# BMS.net
KiCad netlist of a schematic drawn in Altium Designer
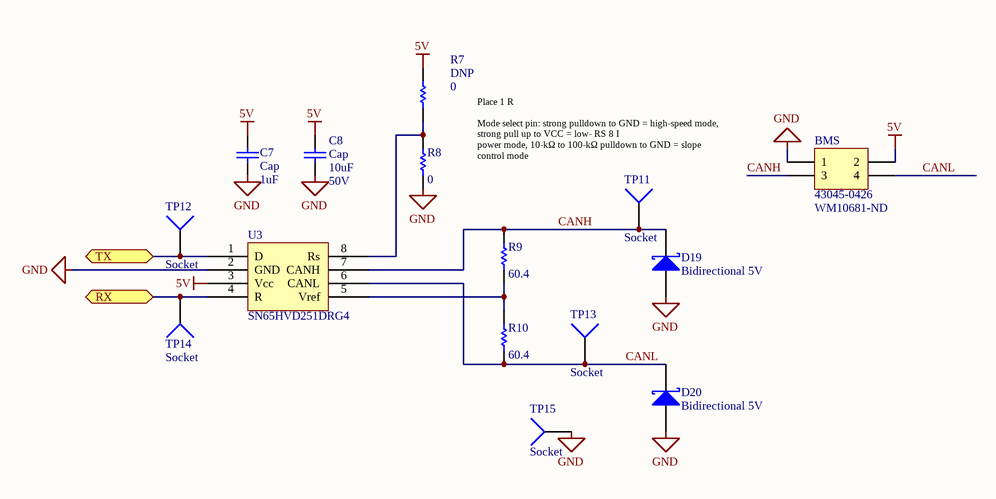
[diagram p0: BMS.SchDoc]

(export (version "E")
  (design (tool "Eeschema 10.0.6"))
  (components
    (comp (ref "BMS")
      (value "43045-0426")
      (footprint "43045-0426")
      (description "Header, 2-Pin, Dual row")
      (fields (field (name "VENDOR PART NUMBER") "WM10681-ND") (field (name "PUBLISHER") "Altium Limited"))
      (libsource (lib "Miscellaneous Connectors") (part "Header 2X2"))
    )
    (comp (ref "C7")
      (value "Cap")
      (footprint "RESC3116X65N")
      (description "Capacitor")
      (fields
        (field (name "ALTIUM_VALUE") "1uF")
        (field (name "MANUFACTURER PART NUMBER") "CL31B105KCHNNNE")
        (field (name "VENDOR PART NUMBER") "1276-1838-1-ND")
      )
      (libsource (lib "Miscellaneous Devices") (part "Cap"))
    )
    (comp (ref "C8")
      (value "Cap")
      (footprint "CAPC3216X180N")
      (description "Capacitor")
      (fields
        (field (name "ALTIUM_VALUE") "10uF")
        (field (name "MANUFACTURER PART NUMBER") "CL31A106MBHNNNE")
        (field (name "VENDOR PART NUMBER") "1276-6736-1-ND")
        (field (name "VOLTAGE RATING") "50V")
      )
      (libsource (lib "Miscellaneous Devices") (part "Cap"))
    )
    (comp (ref "D19")
      (value "Bidirectional 5V")
      (footprint "THRMC0603X33N")
      (description "TVS")
      (fields
        (field (name "MANUFACTURER PART NUMBER") "CPDUC5V0R-HF")
        (field (name "VENDOR PART NUMBER") "641-1764-1-ND")
      )
      (libsource (lib "Miscellaneous Devices") (part "Diode 10TQ040"))
    )
    (comp (ref "D20")
      (value "Bidirectional 5V")
      (footprint "THRMC0603X33N")
      (description "TVS")
      (fields
        (field (name "MANUFACTURER PART NUMBER") "CPDUC5V0R-HF")
        (field (name "VENDOR PART NUMBER") "641-1764-1-ND")
      )
      (libsource (lib "Miscellaneous Devices") (part "Diode 10TQ040"))
    )
    (comp (ref "R7")
      (value "0")
      (footprint "0402")
      (description "Resistor")
      (fields
        (field (name "MANUFACTURER PART NUMBER") "RC0402FR-070RL")
        (field (name "VENDOR PART NUMBER") "311-0.0LRCT-ND")
        (field (name "DNP") "DNP")
      )
      (libsource (lib "Miscellaneous Devices") (part "Res1"))
    )
    (comp (ref "R8")
      (value "0")
      (footprint "0402")
      (description "Resistor")
      (fields
        (field (name "MANUFACTURER PART NUMBER") "RC0402FR-070RL")
        (field (name "VENDOR PART NUMBER") "311-0.0LRCT-ND")
      )
      (libsource (lib "Miscellaneous Devices") (part "Res1"))
    )
    (comp (ref "R9")
      (value "60.4")
      (footprint "0402")
      (description "Resistor")
      (fields
        (field (name "MANUFACTURER PART NUMBER") "RC0402FR-0760R4L")
        (field (name "VENDOR PART NUMBER") "311-60.4LRCT-ND")
      )
      (libsource (lib "Miscellaneous Devices") (part "Res1"))
    )
    (comp (ref "R10")
      (value "60.4")
      (footprint "0402")
      (description "Resistor")
      (fields
        (field (name "MANUFACTURER PART NUMBER") "RC0402FR-0760R4L")
        (field (name "VENDOR PART NUMBER") "311-60.4LRCT-ND")
      )
      (libsource (lib "Miscellaneous Devices") (part "Res1"))
    )
    (comp (ref "TP11")
      (value "Socket")
      (footprint "5006")
      (fields
        (field (name "MANUFACTURER PART NUMBER") "5006")
        (field (name "VENDOR PART NUMBER") "36-5006-ND")
        (field (name "PUBLISHER") "Altium Limited")
      )
      (libsource (lib "Miscellaneous Connectors") (part "Socket"))
    )
    (comp (ref "TP12")
      (value "Socket")
      (footprint "5006")
      (fields
        (field (name "MANUFACTURER PART NUMBER") "5006")
        (field (name "VENDOR PART NUMBER") "36-5006-ND")
        (field (name "PUBLISHER") "Altium Limited")
      )
      (libsource (lib "Miscellaneous Connectors") (part "Socket"))
    )
    (comp (ref "TP13")
      (value "Socket")
      (footprint "5006")
      (fields
        (field (name "MANUFACTURER PART NUMBER") "5006")
        (field (name "VENDOR PART NUMBER") "36-5006-ND")
        (field (name "PUBLISHER") "Altium Limited")
      )
      (libsource (lib "Miscellaneous Connectors") (part "Socket"))
    )
    (comp (ref "TP14")
      (value "Socket")
      (footprint "5006")
      (fields
        (field (name "MANUFACTURER PART NUMBER") "5006")
        (field (name "VENDOR PART NUMBER") "36-5006-ND")
        (field (name "PUBLISHER") "Altium Limited")
      )
      (libsource (lib "Miscellaneous Connectors") (part "Socket"))
    )
    (comp (ref "TP15")
      (value "Socket")
      (footprint "5006")
      (fields
        (field (name "MANUFACTURER PART NUMBER") "5006")
        (field (name "VENDOR PART NUMBER") "36-5006-ND")
        (field (name "PUBLISHER") "Altium Limited")
      )
      (libsource (lib "Miscellaneous Connectors") (part "Socket"))
    )
    (comp (ref "U3")
      (value "SN65HVD251DRG4")
      (footprint "SOIC127P599X175-8N")
      (fields (field (name "VENDOR PART NUMBER") "296-21805-1-ND"))
      (libsource (lib "BeagleCape") (part "SN65HVD251DRG4"))
    )
  )
  (nets
    (net (code "1") (name "/CANH") (class "Default")
      (node (ref "BMS") (pin "3") (pinfunction "3_3") (pintype "passive"))
      (node (ref "D19") (pin "1") (pinfunction "K_1") (pintype "passive"))
      (node (ref "R9") (pin "1") (pinfunction "1_1") (pintype "passive"))
      (node (ref "TP11") (pin "1") (pinfunction "1_1") (pintype "passive"))
      (node (ref "U3") (pin "7") (pinfunction "CANH_7") (pintype "passive"))
    )
    (net (code "2") (name "/CANL") (class "Default")
      (node (ref "BMS") (pin "4") (pinfunction "4_4") (pintype "passive"))
      (node (ref "D20") (pin "1") (pinfunction "K_1") (pintype "passive"))
      (node (ref "R10") (pin "2") (pinfunction "2_2") (pintype "passive"))
      (node (ref "TP13") (pin "1") (pinfunction "1_1") (pintype "passive"))
      (node (ref "U3") (pin "6") (pinfunction "CANL_6") (pintype "passive"))
    )
    (net (code "3") (name "/RX") (class "Default")
      (node (ref "TP14") (pin "1") (pinfunction "1_1") (pintype "passive"))
      (node (ref "U3") (pin "4") (pinfunction "R_4") (pintype "passive"))
    )
    (net (code "4") (name "/TX") (class "Default")
      (node (ref "TP12") (pin "1") (pinfunction "1_1") (pintype "passive"))
      (node (ref "U3") (pin "1") (pinfunction "D_1") (pintype "passive"))
    )
    (net (code "5") (name "5V") (class "Default")
      (node (ref "BMS") (pin "2") (pinfunction "2_2") (pintype "passive"))
      (node (ref "C7") (pin "2") (pinfunction "2_2") (pintype "passive"))
      (node (ref "C8") (pin "2") (pinfunction "2_2") (pintype "passive"))
      (node (ref "R7") (pin "1") (pinfunction "1_1") (pintype "passive"))
      (node (ref "U3") (pin "3") (pinfunction "Vcc_3") (pintype "passive"))
    )
    (net (code "6") (name "GND") (class "Default")
      (node (ref "BMS") (pin "1") (pinfunction "1_1") (pintype "passive"))
      (node (ref "C7") (pin "1") (pinfunction "1_1") (pintype "passive"))
      (node (ref "C8") (pin "1") (pinfunction "1_1") (pintype "passive"))
      (node (ref "D19") (pin "3") (pinfunction "A_3") (pintype "passive"))
      (node (ref "D20") (pin "3") (pinfunction "A_3") (pintype "passive"))
      (node (ref "R8") (pin "2") (pinfunction "2_2") (pintype "passive"))
      (node (ref "TP15") (pin "1") (pinfunction "1_1") (pintype "passive"))
      (node (ref "U3") (pin "2") (pinfunction "GND_2") (pintype "passive"))
    )
    (net (code "7") (name "Net-(U3-Rs)") (class "Default")
      (node (ref "R7") (pin "2") (pinfunction "2_2") (pintype "passive"))
      (node (ref "R8") (pin "1") (pinfunction "1_1") (pintype "passive"))
      (node (ref "U3") (pin "8") (pinfunction "Rs_8") (pintype "passive"))
    )
    (net (code "8") (name "Net-(U3-Vref)") (class "Default")
      (node (ref "R10") (pin "1") (pinfunction "1_1") (pintype "passive"))
      (node (ref "R9") (pin "2") (pinfunction "2_2") (pintype "passive"))
      (node (ref "U3") (pin "5") (pinfunction "Vref_5") (pintype "passive"))
    )
  )
)
